# Power.net
KiCad netlist of a schematic drawn in Altium Designer
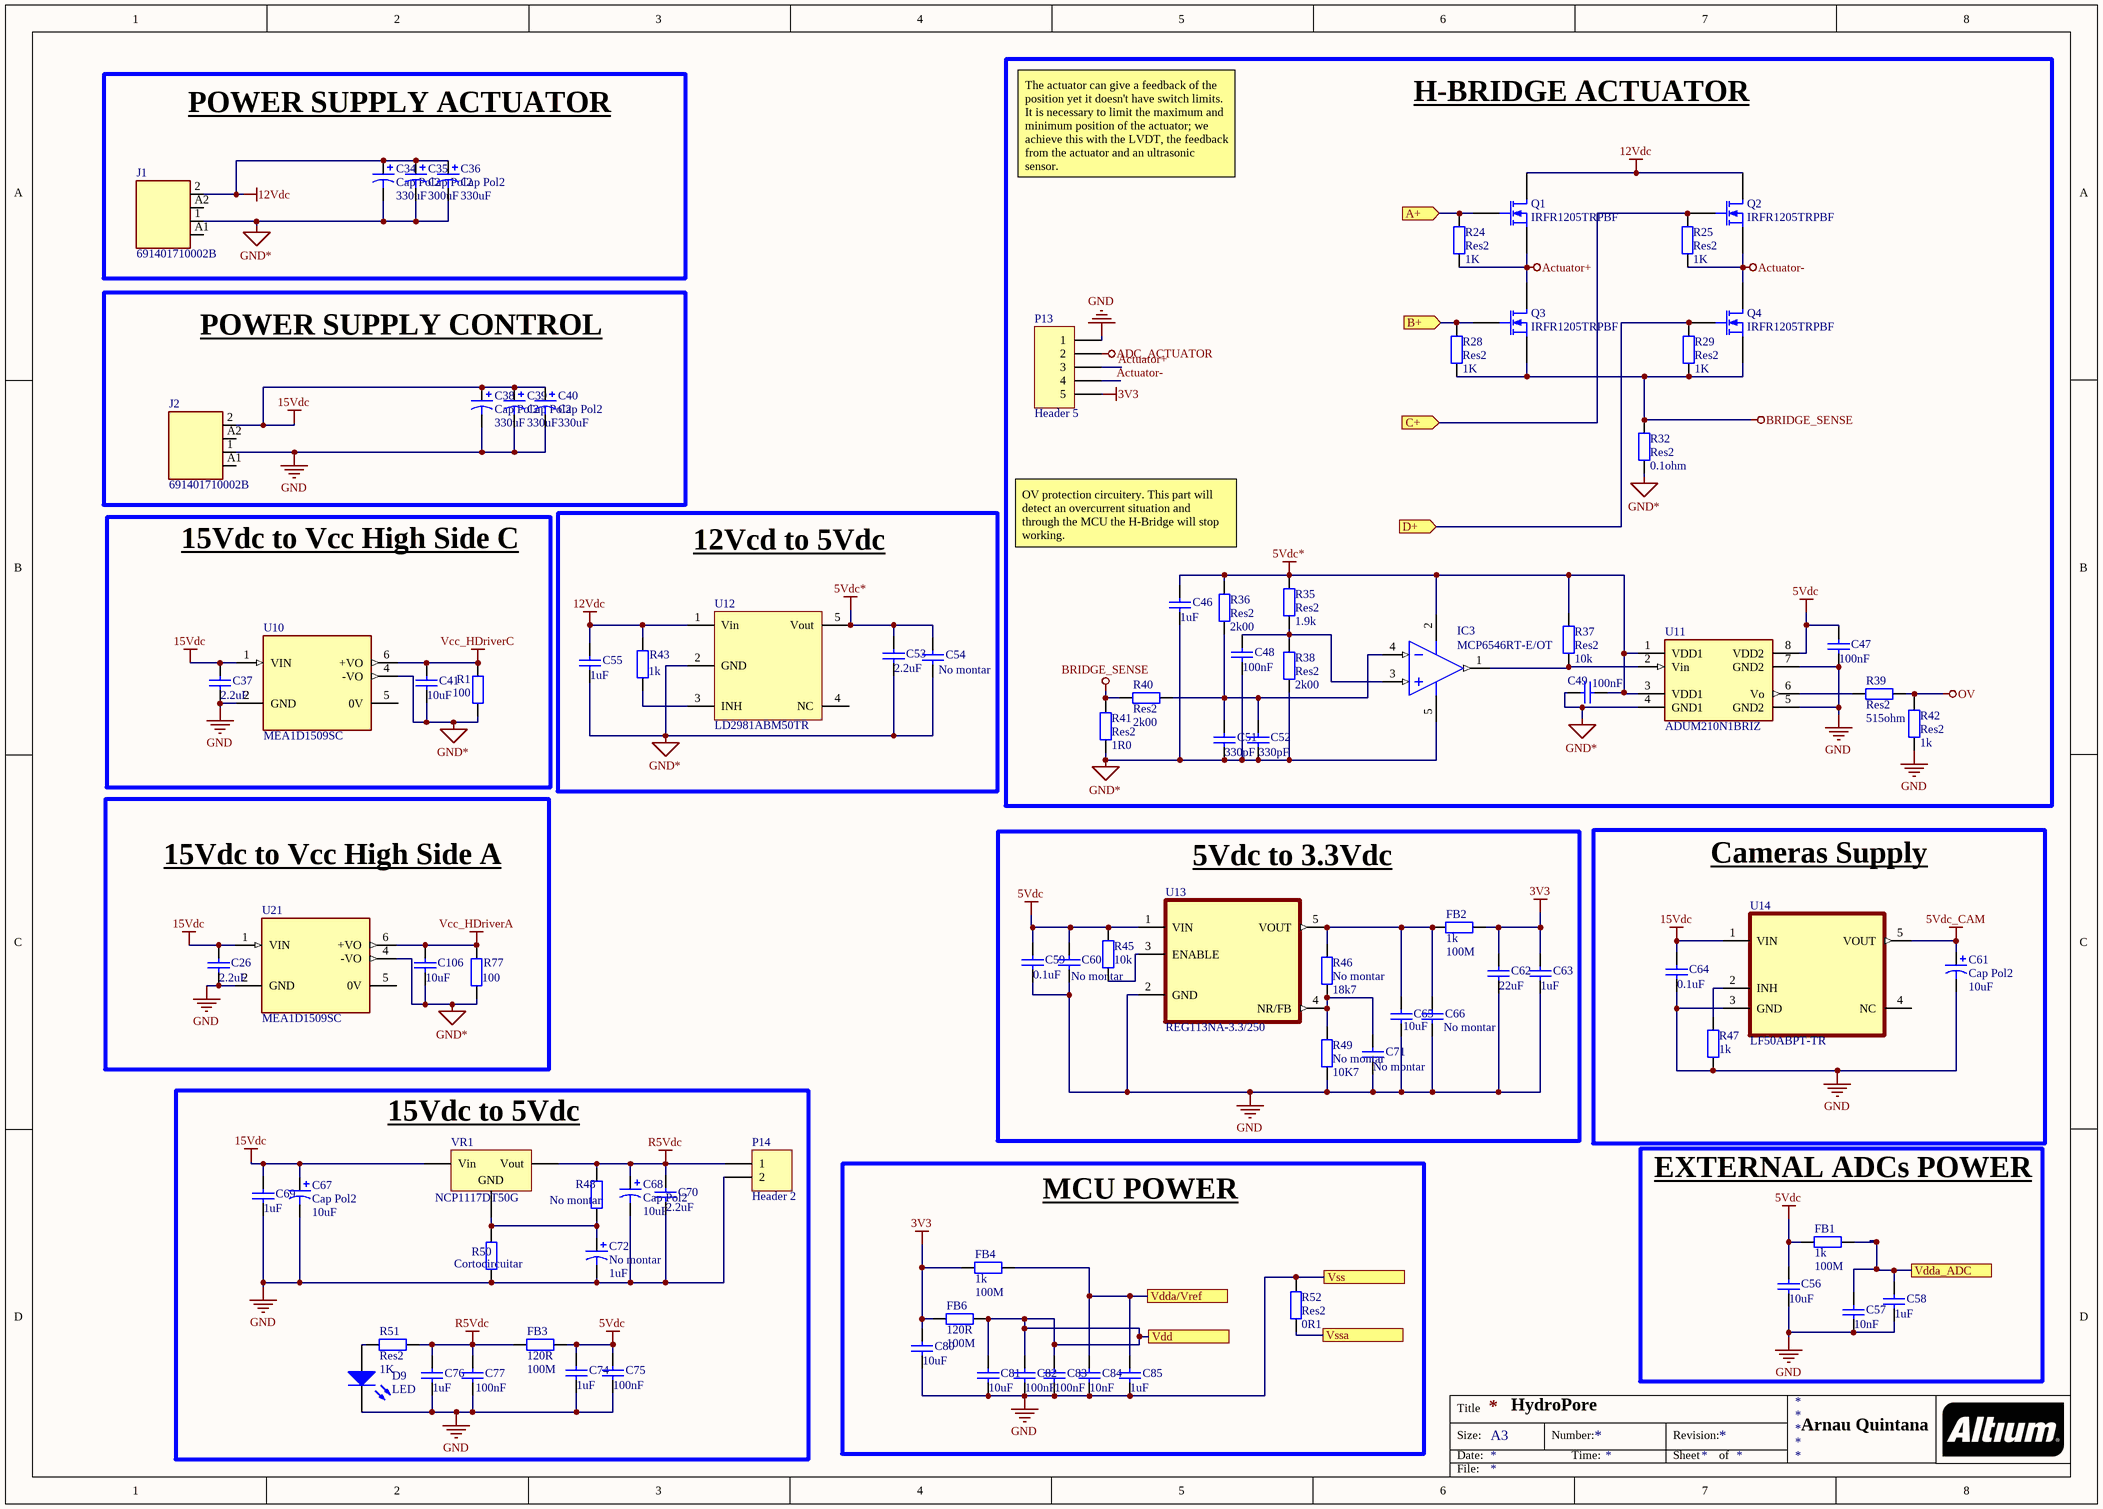
[diagram p0: Power.SchDoc]

(export (version "E")
  (design (tool "Eeschema 10.0.6"))
  (components
    (comp (ref "C26")
      (value "2.2uF")
      (footprint "Miscellaneous Devices:0603 - duplicate")
      (description "Capacitor")
      (fields (field (name "Comment") "Cap") (field (name "PUBLISHER") "Altium Limited"))
      (libsource (lib "Miscellaneous Devices") (part "Cap"))
    )
    (comp (ref "C34")
      (value "Cap Pol2")
      (footprint "Miscellaneous Devices:ElectrolythicCap_5mm")
      (description "Polarized Capacitor (Axial)")
      (fields (field (name "ALTIUM_VALUE") "330uF") (field (name "PUBLISHER") "Altium Limited"))
      (libsource (lib "Miscellaneous Devices") (part "Cap Pol2"))
    )
    (comp (ref "C35")
      (value "Cap Pol2")
      (footprint "Miscellaneous Devices:ElectrolythicCap_5mm")
      (description "Polarized Capacitor (Axial)")
      (fields (field (name "ALTIUM_VALUE") "300uF") (field (name "PUBLISHER") "Altium Limited"))
      (libsource (lib "Miscellaneous Devices") (part "Cap Pol2"))
    )
    (comp (ref "C36")
      (value "Cap Pol2")
      (footprint "Miscellaneous Devices:ElectrolythicCap_5mm")
      (description "Polarized Capacitor (Axial)")
      (fields (field (name "ALTIUM_VALUE") "330uF") (field (name "PUBLISHER") "Altium Limited"))
      (libsource (lib "Miscellaneous Devices") (part "Cap Pol2"))
    )
    (comp (ref "C37")
      (value "2.2uF")
      (footprint "Miscellaneous Devices:0603 - duplicate")
      (description "Capacitor")
      (fields (field (name "Comment") "Cap") (field (name "PUBLISHER") "Altium Limited"))
      (libsource (lib "Miscellaneous Devices") (part "Cap"))
    )
    (comp (ref "C38")
      (value "Cap Pol2")
      (footprint "Miscellaneous Devices:ElectrolythicCap_5mm")
      (description "Polarized Capacitor (Axial)")
      (fields (field (name "ALTIUM_VALUE") "330uF") (field (name "PUBLISHER") "Altium Limited"))
      (libsource (lib "Miscellaneous Devices") (part "Cap Pol2"))
    )
    (comp (ref "C39")
      (value "Cap Pol2")
      (footprint "Miscellaneous Devices:ElectrolythicCap_5mm")
      (description "Polarized Capacitor (Axial)")
      (fields (field (name "ALTIUM_VALUE") "330uF") (field (name "PUBLISHER") "Altium Limited"))
      (libsource (lib "Miscellaneous Devices") (part "Cap Pol2"))
    )
    (comp (ref "C40")
      (value "Cap Pol2")
      (footprint "Miscellaneous Devices:ElectrolythicCap_5mm")
      (description "Polarized Capacitor (Axial)")
      (fields (field (name "ALTIUM_VALUE") "330uF") (field (name "PUBLISHER") "Altium Limited"))
      (libsource (lib "Miscellaneous Devices") (part "Cap Pol2"))
    )
    (comp (ref "C41")
      (value "10uF")
      (footprint "Miscellaneous Devices:0603 - duplicate")
      (description "Capacitor")
      (fields (field (name "Comment") "Cap") (field (name "PUBLISHER") "Altium Limited"))
      (libsource (lib "Miscellaneous Devices") (part "Cap"))
    )
    (comp (ref "C46")
      (value "1uF")
      (footprint "Miscellaneous Devices:0603 - duplicate")
      (description "Capacitor")
      (fields (field (name "Comment") "Cap") (field (name "PUBLISHER") "Altium Limited"))
      (libsource (lib "Miscellaneous Devices") (part "Cap"))
    )
    (comp (ref "C47")
      (value "100nF")
      (footprint "Miscellaneous Devices:0603 - duplicate")
      (description "Capacitor")
      (fields (field (name "Comment") "Cap") (field (name "PUBLISHER") "Altium Limited"))
      (libsource (lib "Miscellaneous Devices") (part "Cap"))
    )
    (comp (ref "C48")
      (value "100nF")
      (footprint "Miscellaneous Devices:0603 - duplicate")
      (description "Capacitor")
      (fields (field (name "Comment") "Cap") (field (name "PUBLISHER") "Altium Limited"))
      (libsource (lib "Miscellaneous Devices") (part "Cap"))
    )
    (comp (ref "C49")
      (value "100nF")
      (footprint "Miscellaneous Devices:0603 - duplicate")
      (description "Capacitor")
      (fields (field (name "Comment") "Cap") (field (name "PUBLISHER") "Altium Limited"))
      (libsource (lib "Miscellaneous Devices") (part "Cap"))
    )
    (comp (ref "C51")
      (value "330pF")
      (footprint "Miscellaneous Devices:0603 - duplicate")
      (description "Capacitor")
      (fields (field (name "Comment") "Cap") (field (name "PUBLISHER") "Altium Limited"))
      (libsource (lib "Miscellaneous Devices") (part "Cap"))
    )
    (comp (ref "C52")
      (value "330pF")
      (footprint "Miscellaneous Devices:0603 - duplicate")
      (description "Capacitor")
      (fields (field (name "Comment") "Cap") (field (name "PUBLISHER") "Altium Limited"))
      (libsource (lib "Miscellaneous Devices") (part "Cap"))
    )
    (comp (ref "C53")
      (value "2.2uF")
      (footprint "Miscellaneous Devices:0603 - duplicate")
      (description "Capacitor")
      (fields (field (name "Comment") "Cap") (field (name "PUBLISHER") "Altium Limited"))
      (libsource (lib "Miscellaneous Devices") (part "Cap"))
    )
    (comp (ref "C54")
      (value "No montar")
      (footprint "Miscellaneous Devices:0603 - duplicate")
      (description "Capacitor")
      (fields (field (name "PUBLISHER") "Altium Limited"))
      (libsource (lib "Miscellaneous Devices") (part "Cap"))
    )
    (comp (ref "C55")
      (value "1uF")
      (footprint "Miscellaneous Devices:0603 - duplicate")
      (description "Capacitor")
      (fields (field (name "Comment") "Cap") (field (name "PUBLISHER") "Altium Limited"))
      (libsource (lib "Miscellaneous Devices") (part "Cap"))
    )
    (comp (ref "C56")
      (value "10uF")
      (footprint "Miscellaneous Devices:0603 - duplicate")
      (description "Capacitor")
      (fields (field (name "Comment") "Cap") (field (name "PUBLISHER") "Altium Limited"))
      (libsource (lib "Miscellaneous Devices") (part "Cap"))
    )
    (comp (ref "C57")
      (value "10nF")
      (footprint "Miscellaneous Devices:0603 - duplicate")
      (description "Capacitor")
      (fields (field (name "Comment") "Cap") (field (name "PUBLISHER") "Altium Limited"))
      (libsource (lib "Miscellaneous Devices") (part "Cap"))
    )
    (comp (ref "C58")
      (value "1uF")
      (footprint "Miscellaneous Devices:0603 - duplicate")
      (description "Capacitor")
      (fields (field (name "Comment") "Cap") (field (name "PUBLISHER") "Altium Limited"))
      (libsource (lib "Miscellaneous Devices") (part "Cap"))
    )
    (comp (ref "C59")
      (value "0.1uF")
      (footprint "Miscellaneous Devices:0603 - duplicate")
      (description "Capacitor")
      (fields (field (name "Comment") "Cap") (field (name "PUBLISHER") "Altium Limited"))
      (libsource (lib "Miscellaneous Devices") (part "Cap"))
    )
    (comp (ref "C60")
      (value "No montar")
      (footprint "Miscellaneous Devices:0603 - duplicate")
      (description "Capacitor")
      (fields (field (name "PUBLISHER") "Altium Limited"))
      (libsource (lib "Miscellaneous Devices") (part "Cap"))
    )
    (comp (ref "C61")
      (value "Cap Pol2")
      (footprint "Miscellaneous Devices:ElectrolythicCap_2mm")
      (description "Polarized Capacitor (Axial)")
      (fields (field (name "ALTIUM_VALUE") "10uF") (field (name "PUBLISHER") "Altium Limited"))
      (libsource (lib "Miscellaneous Devices") (part "Cap Pol2"))
    )
    (comp (ref "C62")
      (value "22uF")
      (footprint "Miscellaneous Devices:0603 - duplicate")
      (description "Capacitor")
      (fields (field (name "Comment") "Cap") (field (name "PUBLISHER") "Altium Limited"))
      (libsource (lib "Miscellaneous Devices") (part "Cap"))
    )
    (comp (ref "C63")
      (value "1uF")
      (footprint "Miscellaneous Devices:0603 - duplicate")
      (description "Capacitor")
      (fields (field (name "Comment") "Cap") (field (name "PUBLISHER") "Altium Limited"))
      (libsource (lib "Miscellaneous Devices") (part "Cap"))
    )
    (comp (ref "C64")
      (value "0.1uF")
      (footprint "Miscellaneous Devices:0603 - duplicate")
      (description "Capacitor")
      (fields (field (name "Comment") "Cap") (field (name "PUBLISHER") "Altium Limited"))
      (libsource (lib "Miscellaneous Devices") (part "Cap"))
    )
    (comp (ref "C65")
      (value "10uF")
      (footprint "Miscellaneous Devices:0603 - duplicate")
      (description "Capacitor")
      (fields (field (name "PUBLISHER") "Altium Limited"))
      (libsource (lib "Miscellaneous Devices") (part "Cap"))
    )
    (comp (ref "C66")
      (value "No montar")
      (footprint "Miscellaneous Devices:0603 - duplicate")
      (description "Capacitor")
      (fields (field (name "PUBLISHER") "Altium Limited"))
      (libsource (lib "Miscellaneous Devices") (part "Cap"))
    )
    (comp (ref "C67")
      (value "Cap Pol2")
      (footprint "Miscellaneous Devices:ElectrolythicCap_2mm")
      (description "Polarized Capacitor (Axial)")
      (fields (field (name "ALTIUM_VALUE") "10uF") (field (name "PUBLISHER") "Altium Limited"))
      (libsource (lib "Miscellaneous Devices") (part "Cap Pol2"))
    )
    (comp (ref "C68")
      (value "Cap Pol2")
      (footprint "Miscellaneous Devices:ElectrolythicCap_2mm")
      (description "Polarized Capacitor (Axial)")
      (fields (field (name "ALTIUM_VALUE") "10uF") (field (name "PUBLISHER") "Altium Limited"))
      (libsource (lib "Miscellaneous Devices") (part "Cap Pol2"))
    )
    (comp (ref "C69")
      (value "1uF")
      (footprint "Miscellaneous Devices:0603 - duplicate")
      (description "Capacitor")
      (fields (field (name "Comment") "Cap") (field (name "PUBLISHER") "Altium Limited"))
      (libsource (lib "Miscellaneous Devices") (part "Cap"))
    )
    (comp (ref "C70")
      (value "2.2uF")
      (footprint "Miscellaneous Devices:0603 - duplicate")
      (description "Capacitor")
      (fields (field (name "Comment") "Cap") (field (name "PUBLISHER") "Altium Limited"))
      (libsource (lib "Miscellaneous Devices") (part "Cap"))
    )
    (comp (ref "C71")
      (value "No montar")
      (footprint "Miscellaneous Devices:0603 - duplicate")
      (description "Capacitor")
      (fields (field (name "Comment") "0.01uF") (field (name "PUBLISHER") "Altium Limited"))
      (libsource (lib "Miscellaneous Devices") (part "Cap"))
    )
    (comp (ref "C72")
      (value "No montar")
      (footprint "Miscellaneous Devices:ElectrolythicCap_2mm")
      (description "Polarized Capacitor (Axial)")
      (fields (field (name "ALTIUM_VALUE") "1uF") (field (name "PUBLISHER") "Altium Limited"))
      (libsource (lib "Miscellaneous Devices") (part "Cap Pol2"))
    )
    (comp (ref "C74")
      (value "1uF")
      (footprint "Miscellaneous Devices:0603 - duplicate")
      (description "Capacitor")
      (fields (field (name "Comment") "Cap") (field (name "PUBLISHER") "Altium Limited"))
      (libsource (lib "Miscellaneous Devices") (part "Cap"))
    )
    (comp (ref "C75")
      (value "100nF")
      (footprint "Miscellaneous Devices:0603 - duplicate")
      (description "Capacitor")
      (fields (field (name "Comment") "Cap") (field (name "PUBLISHER") "Altium Limited"))
      (libsource (lib "Miscellaneous Devices") (part "Cap"))
    )
    (comp (ref "C76")
      (value "1uF")
      (footprint "Miscellaneous Devices:0603 - duplicate")
      (description "Capacitor")
      (fields (field (name "Comment") "Cap") (field (name "PUBLISHER") "Altium Limited"))
      (libsource (lib "Miscellaneous Devices") (part "Cap"))
    )
    (comp (ref "C77")
      (value "100nF")
      (footprint "Miscellaneous Devices:0603 - duplicate")
      (description "Capacitor")
      (fields (field (name "Comment") "Cap") (field (name "PUBLISHER") "Altium Limited"))
      (libsource (lib "Miscellaneous Devices") (part "Cap"))
    )
    (comp (ref "C80")
      (value "10uF")
      (footprint "Miscellaneous Devices:0603 - duplicate")
      (description "Capacitor")
      (fields (field (name "Comment") "Cap") (field (name "PUBLISHER") "Altium Limited"))
      (libsource (lib "Miscellaneous Devices") (part "Cap"))
    )
    (comp (ref "C81")
      (value "10uF")
      (footprint "Miscellaneous Devices:0603 - duplicate")
      (description "Capacitor")
      (fields (field (name "Comment") "Cap") (field (name "PUBLISHER") "Altium Limited"))
      (libsource (lib "Miscellaneous Devices") (part "Cap"))
    )
    (comp (ref "C82")
      (value "100nF")
      (footprint "Miscellaneous Devices:0603 - duplicate")
      (description "Capacitor")
      (fields (field (name "Comment") "Cap") (field (name "PUBLISHER") "Altium Limited"))
      (libsource (lib "Miscellaneous Devices") (part "Cap"))
    )
    (comp (ref "C83")
      (value "100nF")
      (footprint "Miscellaneous Devices:0603 - duplicate")
      (description "Capacitor")
      (fields (field (name "Comment") "Cap") (field (name "PUBLISHER") "Altium Limited"))
      (libsource (lib "Miscellaneous Devices") (part "Cap"))
    )
    (comp (ref "C84")
      (value "10nF")
      (footprint "Miscellaneous Devices:0603 - duplicate")
      (description "Capacitor")
      (fields (field (name "Comment") "Cap") (field (name "PUBLISHER") "Altium Limited"))
      (libsource (lib "Miscellaneous Devices") (part "Cap"))
    )
    (comp (ref "C85")
      (value "1uF")
      (footprint "Miscellaneous Devices:0603 - duplicate")
      (description "Capacitor")
      (fields (field (name "Comment") "Cap") (field (name "PUBLISHER") "Altium Limited"))
      (libsource (lib "Miscellaneous Devices") (part "Cap"))
    )
    (comp (ref "C106")
      (value "10uF")
      (footprint "Miscellaneous Devices:0603 - duplicate")
      (description "Capacitor")
      (fields (field (name "Comment") "Cap") (field (name "PUBLISHER") "Altium Limited"))
      (libsource (lib "Miscellaneous Devices") (part "Cap"))
    )
    (comp (ref "D9")
      (value "LED")
      (footprint "Miscellaneous Devices:LED 1206")
      (description "Typical RED, GREEN, YELLOW, AMBER GaAs LED")
      (fields (field (name "PUBLISHER") "Altium Limited"))
      (libsource (lib "Miscellaneous Devices") (part "LED"))
    )
    (comp (ref "FB1")
      (value "1k")
      (footprint "Miscellaneous Devices:0603 - duplicate")
      (description "Resistor")
      (fields (field (name "ALTIUM_VALUE") "100M") (field (name "PUBLISHER") "Altium Limited"))
      (libsource (lib "") (part "Res2_2"))
    )
    (comp (ref "FB2")
      (value "1k")
      (footprint "Miscellaneous Devices:0603 - duplicate")
      (description "Resistor")
      (fields (field (name "ALTIUM_VALUE") "100M") (field (name "PUBLISHER") "Altium Limited"))
      (libsource (lib "") (part "Res2_2"))
    )
    (comp (ref "FB3")
      (value "120R")
      (footprint "Miscellaneous Devices:0603 - duplicate")
      (description "Resistor")
      (fields (field (name "ALTIUM_VALUE") "100M") (field (name "PUBLISHER") "Altium Limited"))
      (libsource (lib "") (part "Res2_2"))
    )
    (comp (ref "FB4")
      (value "1k")
      (footprint "Miscellaneous Devices:0603 - duplicate")
      (description "Resistor")
      (fields (field (name "ALTIUM_VALUE") "100M") (field (name "PUBLISHER") "Altium Limited"))
      (libsource (lib "") (part "Res2_2"))
    )
    (comp (ref "FB6")
      (value "120R")
      (footprint "Miscellaneous Devices:0603 - duplicate")
      (description "Resistor")
      (fields (field (name "ALTIUM_VALUE") "100M") (field (name "PUBLISHER") "Altium Limited"))
      (libsource (lib "") (part "Res2_2"))
    )
    (comp (ref "IC3")
      (value "MCP6546RT-E/OT")
      (footprint "Miscellaneous Devices:SOT23-5_N")
      (description "Operational Amplifier")
      (fields (field (name "PUBLISHER") "Altium Limited"))
      (libsource (lib "Miscellaneous Devices") (part "MCP6546RT-E/OT"))
    )
    (comp (ref "J1")
      (value "691401710002B")
      (footprint "Miscellaneous Connectors:691401710002B")
      (fields (field (name "MF") "WÃ¼rth Elektronik"))
      (libsource (lib "Miscellaneous Connectors") (part "691401710002B"))
    )
    (comp (ref "J2")
      (value "691401710002B")
      (footprint "Miscellaneous Connectors:691401710002B")
      (fields (field (name "MF") "WÃ¼rth Elektronik"))
      (libsource (lib "Miscellaneous Connectors") (part "691401710002B"))
    )
    (comp (ref "P13")
      (value "Header 5")
      (footprint "Miscellaneous Connectors:regleta_5")
      (description "Header, 5-Pin")
      (fields (field (name "PUBLISHER") "Altium Limited"))
      (libsource (lib "Miscellaneous Connectors") (part "Header 5"))
    )
    (comp (ref "P14")
      (value "Header 2")
      (footprint "HDR1X2")
      (description "Header, 2-Pin")
      (fields (field (name "PUBLISHER") "Altium Limited"))
      (libsource (lib "Miscellaneous Connectors") (part "Header 2"))
    )
    (comp (ref "Q1")
      (value "IRFR1205TRPBF")
      (footprint "Miscellaneous Devices:Infineon_PG-TO252-3_MFG")
      (description "N-Channel MOSFET")
      (fields (field (name "PUBLISHER") "Altium Limited"))
      (libsource (lib "Miscellaneous Devices") (part "IRFR1205TRPBF"))
    )
    (comp (ref "Q2")
      (value "IRFR1205TRPBF")
      (footprint "Miscellaneous Devices:Infineon_PG-TO252-3_MFG")
      (description "N-Channel MOSFET")
      (fields (field (name "PUBLISHER") "Altium Limited"))
      (libsource (lib "Miscellaneous Devices") (part "IRFR1205TRPBF"))
    )
    (comp (ref "Q3")
      (value "IRFR1205TRPBF")
      (footprint "Miscellaneous Devices:Infineon_PG-TO252-3_MFG")
      (description "N-Channel MOSFET")
      (fields (field (name "PUBLISHER") "Altium Limited"))
      (libsource (lib "Miscellaneous Devices") (part "IRFR1205TRPBF"))
    )
    (comp (ref "Q4")
      (value "IRFR1205TRPBF")
      (footprint "Miscellaneous Devices:Infineon_PG-TO252-3_MFG")
      (description "N-Channel MOSFET")
      (fields (field (name "PUBLISHER") "Altium Limited"))
      (libsource (lib "Miscellaneous Devices") (part "IRFR1205TRPBF"))
    )
    (comp (ref "R1")
      (value "100")
      (footprint "Miscellaneous Devices:1206")
      (description "Resistor")
      (fields (field (name "PUBLISHER") "Altium Limited"))
      (libsource (lib "Miscellaneous Devices") (part "Res2"))
    )
    (comp (ref "R24")
      (value "Res2")
      (footprint "Miscellaneous Devices:0603 - duplicate")
      (description "Resistor")
      (fields (field (name "ALTIUM_VALUE") "1K") (field (name "PUBLISHER") "Altium Limited"))
      (libsource (lib "Miscellaneous Devices") (part "Res2"))
    )
    (comp (ref "R25")
      (value "Res2")
      (footprint "Miscellaneous Devices:0603 - duplicate")
      (description "Resistor")
      (fields (field (name "ALTIUM_VALUE") "1K") (field (name "PUBLISHER") "Altium Limited"))
      (libsource (lib "Miscellaneous Devices") (part "Res2"))
    )
    (comp (ref "R28")
      (value "Res2")
      (footprint "Miscellaneous Devices:0603 - duplicate")
      (description "Resistor")
      (fields (field (name "ALTIUM_VALUE") "1K") (field (name "PUBLISHER") "Altium Limited"))
      (libsource (lib "Miscellaneous Devices") (part "Res2"))
    )
    (comp (ref "R29")
      (value "Res2")
      (footprint "Miscellaneous Devices:0603 - duplicate")
      (description "Resistor")
      (fields (field (name "ALTIUM_VALUE") "1K") (field (name "PUBLISHER") "Altium Limited"))
      (libsource (lib "Miscellaneous Devices") (part "Res2"))
    )
    (comp (ref "R32")
      (value "Res2")
      (footprint "Miscellaneous Devices:1206")
      (description "Resistor")
      (fields (field (name "ALTIUM_VALUE") "0.1ohm") (field (name "PUBLISHER") "Altium Limited"))
      (libsource (lib "Miscellaneous Devices") (part "Res2"))
    )
    (comp (ref "R35")
      (value "Res2")
      (footprint "Miscellaneous Devices:0603 - duplicate")
      (description "Resistor")
      (fields (field (name "ALTIUM_VALUE") "1.9k") (field (name "PUBLISHER") "Altium Limited"))
      (libsource (lib "") (part "Res2_3"))
    )
    (comp (ref "R36")
      (value "Res2")
      (footprint "Miscellaneous Devices:0603 - duplicate")
      (description "Resistor")
      (fields (field (name "ALTIUM_VALUE") "2k00") (field (name "PUBLISHER") "Altium Limited"))
      (libsource (lib "") (part "Res2_3"))
    )
    (comp (ref "R37")
      (value "Res2")
      (footprint "Miscellaneous Devices:0603 - duplicate")
      (description "Resistor")
      (fields (field (name "ALTIUM_VALUE") "10k") (field (name "PUBLISHER") "Altium Limited"))
      (libsource (lib "Miscellaneous Devices") (part "Res2"))
    )
    (comp (ref "R38")
      (value "Res2")
      (footprint "Miscellaneous Devices:0603 - duplicate")
      (description "Resistor")
      (fields (field (name "ALTIUM_VALUE") "2k00") (field (name "PUBLISHER") "Altium Limited"))
      (libsource (lib "") (part "Res2_3"))
    )
    (comp (ref "R39")
      (value "Res2")
      (footprint "Miscellaneous Devices:0603 - duplicate")
      (description "Resistor")
      (fields (field (name "ALTIUM_VALUE") "515ohm") (field (name "PUBLISHER") "Altium Limited"))
      (libsource (lib "") (part "Res2_1"))
    )
    (comp (ref "R40")
      (value "Res2")
      (footprint "Miscellaneous Devices:0603 - duplicate")
      (description "Resistor")
      (fields (field (name "ALTIUM_VALUE") "2k00") (field (name "PUBLISHER") "Altium Limited"))
      (libsource (lib "") (part "Res2_2"))
    )
    (comp (ref "R41")
      (value "Res2")
      (footprint "Miscellaneous Devices:1206")
      (description "Resistor")
      (fields (field (name "ALTIUM_VALUE") "1R0") (field (name "PUBLISHER") "Altium Limited"))
      (libsource (lib "Miscellaneous Devices") (part "Res2"))
    )
    (comp (ref "R42")
      (value "Res2")
      (footprint "Miscellaneous Devices:0603 - duplicate")
      (description "Resistor")
      (fields (field (name "ALTIUM_VALUE") "1k") (field (name "PUBLISHER") "Altium Limited"))
      (libsource (lib "") (part "Res2_3"))
    )
    (comp (ref "R43")
      (value "1k")
      (footprint "Miscellaneous Devices:0603 - duplicate")
      (description "Resistor")
      (fields (field (name "PUBLISHER") "Altium Limited"))
      (libsource (lib "Miscellaneous Devices") (part "Res2"))
    )
    (comp (ref "R45")
      (value "10k")
      (footprint "Miscellaneous Devices:0603 - duplicate")
      (description "Resistor")
      (fields (field (name "PUBLISHER") "Altium Limited"))
      (libsource (lib "Miscellaneous Devices") (part "Res2"))
    )
    (comp (ref "R46")
      (value "No montar")
      (footprint "Miscellaneous Devices:0603 - duplicate")
      (description "Resistor")
      (fields (field (name "ALTIUM_VALUE") "18k7") (field (name "PUBLISHER") "Altium Limited"))
      (libsource (lib "Miscellaneous Devices") (part "Res2"))
    )
    (comp (ref "R47")
      (value "1k")
      (footprint "Miscellaneous Devices:0603 - duplicate")
      (description "Resistor")
      (fields (field (name "PUBLISHER") "Altium Limited"))
      (libsource (lib "Miscellaneous Devices") (part "Res2"))
    )
    (comp (ref "R48")
      (value "No montar")
      (footprint "Miscellaneous Devices:0603 - duplicate")
      (description "Resistor")
      (fields (field (name "PUBLISHER") "Altium Limited"))
      (libsource (lib "Miscellaneous Devices") (part "Res2"))
    )
    (comp (ref "R49")
      (value "No montar")
      (footprint "Miscellaneous Devices:0603 - duplicate")
      (description "Resistor")
      (fields (field (name "ALTIUM_VALUE") "10K7") (field (name "PUBLISHER") "Altium Limited"))
      (libsource (lib "Miscellaneous Devices") (part "Res2"))
    )
    (comp (ref "R50")
      (value "Cortocircuitar")
      (footprint "Miscellaneous Devices:0603 - duplicate")
      (description "Resistor")
      (fields (field (name "PUBLISHER") "Altium Limited"))
      (libsource (lib "Miscellaneous Devices") (part "Res2"))
    )
    (comp (ref "R51")
      (value "Res2")
      (footprint "Miscellaneous Devices:0603 - duplicate")
      (description "Resistor")
      (fields (field (name "ALTIUM_VALUE") "1K") (field (name "PUBLISHER") "Altium Limited"))
      (libsource (lib "") (part "Res2_2"))
    )
    (comp (ref "R52")
      (value "Res2")
      (footprint "Miscellaneous Devices:0603 - duplicate")
      (description "Resistor")
      (fields (field (name "ALTIUM_VALUE") "0R1") (field (name "PUBLISHER") "Altium Limited"))
      (libsource (lib "Miscellaneous Devices") (part "Res2"))
    )
    (comp (ref "R77")
      (value "100")
      (footprint "Miscellaneous Devices:1206")
      (description "Resistor")
      (fields (field (name "PUBLISHER") "Altium Limited"))
      (libsource (lib "Miscellaneous Devices") (part "Res2"))
    )
    (comp (ref "U10")
      (value "MEA1D1509SC")
      (footprint "Miscellaneous Devices:CONV_MEA1D1509SC")
      (description "1 W, Dual Independent Output, 7 Pin SIP, 4200 Vdc Isolation, Dc-Dc Converter")
      (fields (field (name "MP") "VQA-S15-D15-SIP") (field (name "MF") "CUI Inc."))
      (libsource (lib "Miscellaneous Devices") (part "MEA1D1509SC"))
    )
    (comp (ref "U11")
      (value "ADUM210N1BRIZ")
      (footprint "Miscellaneous Devices:SOIC127P1031X265-8N")
      (description "Digital Isolator")
      (fields (field (name "MP") "PEME2-S15-D5-S") (field (name "MF") "CUI"))
      (libsource (lib "Miscellaneous Devices") (part "ADUM210N1BRIZ"))
    )
    (comp (ref "U12")
      (value "LD2981ABM50TR")
      (footprint "Miscellaneous Devices:SOT23-5_N")
      (fields (field (name "PUBLISHER") "Altium Limited"))
      (libsource (lib "Miscellaneous Devices") (part "LD2981ABM50TR"))
    )
    (comp (ref "U13")
      (value "REG113NA-3.3/250")
      (footprint "Miscellaneous Devices:SOT23-5_N")
      (description "Dropout Linear  Regulator")
      (fields (field (name "MP") "LP3964EMP-ADJ"))
      (libsource (lib "Miscellaneous Devices") (part "REG113NA-3.3/250"))
    )
    (comp (ref "U14")
      (value "LF50ABPT-TR")
      (footprint "Miscellaneous Devices:DPAK114P990X239-6N")
      (description "Dropout Linear  Regulator")
      (fields (field (name "MP") "LP3964EMP-ADJ"))
      (libsource (lib "Miscellaneous Devices") (part "LF50ABPT-TR"))
    )
    (comp (ref "U21")
      (value "MEA1D1509SC")
      (footprint "Miscellaneous Devices:CONV_MEA1D1509SC")
      (description "1 W, Dual Independent Output, 7 Pin SIP, 4200 Vdc Isolation, Dc-Dc Converter")
      (fields (field (name "MP") "VQA-S15-D15-SIP") (field (name "MF") "CUI Inc."))
      (libsource (lib "Miscellaneous Devices") (part "MEA1D1509SC"))
    )
    (comp (ref "VR1")
      (value "NCP1117DT50G")
      (footprint "D2PAK_N")
      (fields (field (name "PUBLISHER") "Altium Limited"))
      (libsource (lib "Miscellaneous Devices") (part "Volt Reg"))
    )
  )
  (nets
    (net (code "1") (name "/A+") (class "Default")
      (node (ref "Q1") (pin "1") (pinfunction "G_1") (pintype "passive"))
      (node (ref "R24") (pin "2") (pinfunction "2_2") (pintype "passive"))
    )
    (net (code "2") (name "/B+") (class "Default")
      (node (ref "Q3") (pin "1") (pinfunction "G_1") (pintype "passive"))
      (node (ref "R28") (pin "2") (pinfunction "2_2") (pintype "passive"))
    )
    (net (code "3") (name "/C+") (class "Default")
      (node (ref "Q2") (pin "1") (pinfunction "G_1") (pintype "passive"))
      (node (ref "R25") (pin "2") (pinfunction "2_2") (pintype "passive"))
    )
    (net (code "4") (name "/D+") (class "Default")
      (node (ref "Q4") (pin "1") (pinfunction "G_1") (pintype "passive"))
      (node (ref "R29") (pin "2") (pinfunction "2_2") (pintype "passive"))
    )
    (net (code "5") (name "/Vdd") (class "Default")
      (node (ref "C81") (pin "2") (pinfunction "2_2") (pintype "passive"))
      (node (ref "C82") (pin "2") (pinfunction "2_2") (pintype "passive"))
      (node (ref "C83") (pin "2") (pinfunction "2_2") (pintype "passive"))
      (node (ref "FB6") (pin "2") (pinfunction "2_2") (pintype "passive"))
    )
    (net (code "6") (name "/Vdda_ADC") (class "Default")
      (node (ref "C57") (pin "2") (pinfunction "2_2") (pintype "passive"))
      (node (ref "C58") (pin "2") (pinfunction "2_2") (pintype "passive"))
      (node (ref "FB1") (pin "2") (pinfunction "2_2") (pintype "passive"))
    )
    (net (code "7") (name "/Vdda{slash}Vref") (class "Default")
      (node (ref "C84") (pin "2") (pinfunction "2_2") (pintype "passive"))
      (node (ref "C85") (pin "2") (pinfunction "2_2") (pintype "passive"))
      (node (ref "FB4") (pin "2") (pinfunction "2_2") (pintype "passive"))
    )
    (net (code "8") (name "/Vssa") (class "Default")
      (node (ref "R52") (pin "1") (pinfunction "1_1") (pintype "passive"))
    )
    (net (code "9") (name "3V3") (class "Default")
      (node (ref "C62") (pin "2") (pinfunction "2_2") (pintype "passive"))
      (node (ref "C63") (pin "2") (pinfunction "2_2") (pintype "passive"))
      (node (ref "C80") (pin "2") (pinfunction "2_2") (pintype "passive"))
      (node (ref "FB2") (pin "2") (pinfunction "2_2") (pintype "passive"))
      (node (ref "FB4") (pin "1") (pinfunction "1_1") (pintype "passive"))
      (node (ref "FB6") (pin "1") (pinfunction "1_1") (pintype "passive"))
      (node (ref "P13") (pin "5") (pinfunction "5_5") (pintype "passive"))
    )
    (net (code "10") (name "5Vdc") (class "Default")
      (node (ref "C47") (pin "2") (pinfunction "2_2") (pintype "passive"))
      (node (ref "C56") (pin "2") (pinfunction "2_2") (pintype "passive"))
      (node (ref "C59") (pin "2") (pinfunction "2_2") (pintype "passive"))
      (node (ref "C60") (pin "2") (pinfunction "2_2") (pintype "passive"))
      (node (ref "C74") (pin "2") (pinfunction "2_2") (pintype "passive"))
      (node (ref "C75") (pin "2") (pinfunction "2_2") (pintype "passive"))
      (node (ref "FB1") (pin "1") (pinfunction "1_1") (pintype "passive"))
      (node (ref "FB3") (pin "2") (pinfunction "2_2") (pintype "passive"))
      (node (ref "R45") (pin "2") (pinfunction "2_2") (pintype "passive"))
      (node (ref "U11") (pin "8") (pinfunction "VDD2_8") (pintype "power_in"))
      (node (ref "U13") (pin "1") (pinfunction "VIN_1") (pintype "power_in"))
    )
    (net (code "11") (name "5Vdc*") (class "Default")
      (node (ref "C46") (pin "2") (pinfunction "2_2") (pintype "passive"))
      (node (ref "C49") (pin "1") (pinfunction "1_1") (pintype "passive"))
      (node (ref "C53") (pin "2") (pinfunction "2_2") (pintype "passive"))
      (node (ref "C54") (pin "2") (pinfunction "2_2") (pintype "passive"))
      (node (ref "IC3") (pin "2") (pinfunction "V+_2") (pintype "power_in"))
      (node (ref "R35") (pin "1") (pinfunction "1_1") (pintype "passive"))
      (node (ref "R36") (pin "1") (pinfunction "1_1") (pintype "passive"))
      (node (ref "R37") (pin "2") (pinfunction "2_2") (pintype "passive"))
      (node (ref "U11") (pin "1") (pinfunction "VDD1_1") (pintype "power_in"))
      (node (ref "U11") (pin "3") (pinfunction "VDD1_3") (pintype "power_in"))
      (node (ref "U12") (pin "5") (pinfunction "Vout_5") (pintype "passive"))
    )
    (net (code "12") (name "5Vdc_CAM") (class "Default")
      (node (ref "C61") (pin "P") (pinfunction "1_P") (pintype "passive"))
      (node (ref "U14") (pin "5") (pinfunction "VOUT_5") (pintype "output"))
    )
    (net (code "13") (name "12Vdc") (class "Default")
      (node (ref "C34") (pin "P") (pinfunction "1_P") (pintype "passive"))
      (node (ref "C35") (pin "P") (pinfunction "1_P") (pintype "passive"))
      (node (ref "C36") (pin "P") (pinfunction "1_P") (pintype "passive"))
      (node (ref "C55") (pin "2") (pinfunction "2_2") (pintype "passive"))
      (node (ref "J1") (pin "2") (pinfunction "1_2") (pintype "passive"))
      (node (ref "Q1") (pin "2") (pinfunction "D_2") (pintype "passive"))
      (node (ref "Q2") (pin "2") (pinfunction "D_2") (pintype "passive"))
      (node (ref "R43") (pin "2") (pinfunction "2_2") (pintype "passive"))
      (node (ref "U12") (pin "1") (pinfunction "Vin_1") (pintype "passive"))
    )
    (net (code "14") (name "15Vdc") (class "Default")
      (node (ref "C26") (pin "2") (pinfunction "2_2") (pintype "passive"))
      (node (ref "C37") (pin "2") (pinfunction "2_2") (pintype "passive"))
      (node (ref "C38") (pin "P") (pinfunction "1_P") (pintype "passive"))
      (node (ref "C39") (pin "P") (pinfunction "1_P") (pintype "passive"))
      (node (ref "C40") (pin "P") (pinfunction "1_P") (pintype "passive"))
      (node (ref "C64") (pin "2") (pinfunction "2_2") (pintype "passive"))
      (node (ref "C67") (pin "P") (pinfunction "1_P") (pintype "passive"))
      (node (ref "C69") (pin "2") (pinfunction "2_2") (pintype "passive"))
      (node (ref "J2") (pin "2") (pinfunction "1_2") (pintype "passive"))
      (node (ref "U10") (pin "1") (pinfunction "VIN_1") (pintype "input"))
      (node (ref "U14") (pin "1") (pinfunction "VIN_1") (pintype "power_in"))
      (node (ref "U21") (pin "1") (pinfunction "VIN_1") (pintype "input"))
      (node (ref "VR1") (pin "3") (pinfunction "Vin_3") (pintype "passive"))
    )
    (net (code "15") (name "ADC_ACTUATOR") (class "Default")
      (node (ref "P13") (pin "2") (pinfunction "2_2") (pintype "passive"))
    )
    (net (code "16") (name "Actuator+") (class "Default")
      (node (ref "P13") (pin "3") (pinfunction "3_3") (pintype "passive"))
      (node (ref "Q1") (pin "3") (pinfunction "S_3") (pintype "passive"))
      (node (ref "Q3") (pin "2") (pinfunction "D_2") (pintype "passive"))
      (node (ref "R24") (pin "1") (pinfunction "1_1") (pintype "passive"))
    )
    (net (code "17") (name "Actuator-") (class "Default")
      (node (ref "P13") (pin "4") (pinfunction "4_4") (pintype "passive"))
      (node (ref "Q2") (pin "3") (pinfunction "S_3") (pintype "passive"))
      (node (ref "Q4") (pin "2") (pinfunction "D_2") (pintype "passive"))
      (node (ref "R25") (pin "1") (pinfunction "1_1") (pintype "passive"))
    )
    (net (code "18") (name "BRIDGE_SENSE") (class "Default")
      (node (ref "Q3") (pin "3") (pinfunction "S_3") (pintype "passive"))
      (node (ref "Q4") (pin "3") (pinfunction "S_3") (pintype "passive"))
      (node (ref "R28") (pin "1") (pinfunction "1_1") (pintype "passive"))
      (node (ref "R29") (pin "1") (pinfunction "1_1") (pintype "passive"))
      (node (ref "R32") (pin "2") (pinfunction "2_2") (pintype "passive"))
      (node (ref "R40") (pin "1") (pinfunction "1_1") (pintype "passive"))
      (node (ref "R41") (pin "2") (pinfunction "2_2") (pintype "passive"))
    )
    (net (code "19") (name "GND") (class "Default")
      (node (ref "C26") (pin "1") (pinfunction "1_1") (pintype "passive"))
      (node (ref "C37") (pin "1") (pinfunction "1_1") (pintype "passive"))
      (node (ref "C38") (pin "N") (pinfunction "2_N") (pintype "passive"))
      (node (ref "C39") (pin "N") (pinfunction "2_N") (pintype "passive"))
      (node (ref "C40") (pin "N") (pinfunction "2_N") (pintype "passive"))
      (node (ref "C47") (pin "1") (pinfunction "1_1") (pintype "passive"))
      (node (ref "C56") (pin "1") (pinfunction "1_1") (pintype "passive"))
      (node (ref "C57") (pin "1") (pinfunction "1_1") (pintype "passive"))
      (node (ref "C58") (pin "1") (pinfunction "1_1") (pintype "passive"))
      (node (ref "C59") (pin "1") (pinfunction "1_1") (pintype "passive"))
      (node (ref "C60") (pin "1") (pinfunction "1_1") (pintype "passive"))
      (node (ref "C61") (pin "N") (pinfunction "2_N") (pintype "passive"))
      (node (ref "C62") (pin "1") (pinfunction "1_1") (pintype "passive"))
      (node (ref "C63") (pin "1") (pinfunction "1_1") (pintype "passive"))
      (node (ref "C64") (pin "1") (pinfunction "1_1") (pintype "passive"))
      (node (ref "C65") (pin "1") (pinfunction "1_1") (pintype "passive"))
      (node (ref "C66") (pin "1") (pinfunction "1_1") (pintype "passive"))
      (node (ref "C67") (pin "N") (pinfunction "2_N") (pintype "passive"))
      (node (ref "C68") (pin "N") (pinfunction "2_N") (pintype "passive"))
      (node (ref "C69") (pin "1") (pinfunction "1_1") (pintype "passive"))
      (node (ref "C70") (pin "1") (pinfunction "1_1") (pintype "passive"))
      (node (ref "C71") (pin "1") (pinfunction "1_1") (pintype "passive"))
      (node (ref "C72") (pin "N") (pinfunction "2_N") (pintype "passive"))
      (node (ref "C74") (pin "1") (pinfunction "1_1") (pintype "passive"))
      (node (ref "C75") (pin "1") (pinfunction "1_1") (pintype "passive"))
      (node (ref "C76") (pin "1") (pinfunction "1_1") (pintype "passive"))
      (node (ref "C77") (pin "1") (pinfunction "1_1") (pintype "passive"))
      (node (ref "C80") (pin "1") (pinfunction "1_1") (pintype "passive"))
      (node (ref "C81") (pin "1") (pinfunction "1_1") (pintype "passive"))
      (node (ref "C82") (pin "1") (pinfunction "1_1") (pintype "passive"))
      (node (ref "C83") (pin "1") (pinfunction "1_1") (pintype "passive"))
      (node (ref "C84") (pin "1") (pinfunction "1_1") (pintype "passive"))
      (node (ref "C85") (pin "1") (pinfunction "1_1") (pintype "passive"))
      (node (ref "D9") (pin "2") (pinfunction "K_2") (pintype "passive"))
      (node (ref "J2") (pin "1") (pinfunction "2_1") (pintype "passive"))
      (node (ref "P13") (pin "1") (pinfunction "1_1") (pintype "passive"))
      (node (ref "P14") (pin "2") (pinfunction "2_2") (pintype "passive"))
      (node (ref "R42") (pin "2") (pinfunction "2_2") (pintype "passive"))
      (node (ref "R47") (pin "1") (pinfunction "1_1") (pintype "passive"))
      (node (ref "R49") (pin "1") (pinfunction "1_1") (pintype "passive"))
      (node (ref "R50") (pin "1") (pinfunction "1_1") (pintype "passive"))
      (node (ref "R52") (pin "2") (pinfunction "2_2") (pintype "passive"))
      (node (ref "U10") (pin "2") (pinfunction "GND_2") (pintype "power_in"))
      (node (ref "U11") (pin "5") (pinfunction "GND2_5") (pintype "power_in"))
      (node (ref "U11") (pin "7") (pinfunction "GND2_7") (pintype "power_in"))
      (node (ref "U13") (pin "2") (pinfunction "GND_2") (pintype "passive"))
      (node (ref "U14") (pin "3") (pinfunction "GND_3") (pintype "passive"))
      (node (ref "U21") (pin "2") (pinfunction "GND_2") (pintype "power_in"))
    )
    (net (code "20") (name "GND*") (class "Default")
      (node (ref "C106") (pin "1") (pinfunction "1_1") (pintype "passive"))
      (node (ref "C34") (pin "N") (pinfunction "2_N") (pintype "passive"))
      (node (ref "C35") (pin "N") (pinfunction "2_N") (pintype "passive"))
      (node (ref "C36") (pin "N") (pinfunction "2_N") (pintype "passive"))
      (node (ref "C41") (pin "1") (pinfunction "1_1") (pintype "passive"))
      (node (ref "C46") (pin "1") (pinfunction "1_1") (pintype "passive"))
      (node (ref "C48") (pin "1") (pinfunction "1_1") (pintype "passive"))
      (node (ref "C49") (pin "2") (pinfunction "2_2") (pintype "passive"))
      (node (ref "C51") (pin "1") (pinfunction "1_1") (pintype "passive"))
      (node (ref "C52") (pin "1") (pinfunction "1_1") (pintype "passive"))
      (node (ref "C53") (pin "1") (pinfunction "1_1") (pintype "passive"))
      (node (ref "C54") (pin "1") (pinfunction "1_1") (pintype "passive"))
      (node (ref "C55") (pin "1") (pinfunction "1_1") (pintype "passive"))
      (node (ref "IC3") (pin "5") (pinfunction "V-_5") (pintype "power_in"))
      (node (ref "J1") (pin "1") (pinfunction "2_1") (pintype "passive"))
      (node (ref "R1") (pin "1") (pinfunction "1_1") (pintype "passive"))
      (node (ref "R32") (pin "1") (pinfunction "1_1") (pintype "passive"))
      (node (ref "R38") (pin "2") (pinfunction "2_2") (pintype "passive"))
      (node (ref "R41") (pin "1") (pinfunction "1_1") (pintype "passive"))
      (node (ref "R77") (pin "1") (pinfunction "1_1") (pintype "passive"))
      (node (ref "U10") (pin "4") (pinfunction "-VO_4") (pintype "output"))
      (node (ref "U11") (pin "4") (pinfunction "GND1_4") (pintype "power_in"))
      (node (ref "U12") (pin "2") (pinfunction "GND_2") (pintype "passive"))
      (node (ref "U21") (pin "4") (pinfunction "-VO_4") (pintype "output"))
    )
    (net (code "21") (name "Net-(C72-1)") (class "Default")
      (node (ref "C72") (pin "P") (pinfunction "1_P") (pintype "passive"))
      (node (ref "R48") (pin "1") (pinfunction "1_1") (pintype "passive"))
      (node (ref "R50") (pin "2") (pinfunction "2_2") (pintype "passive"))
      (node (ref "VR1") (pin "1") (pinfunction "GND_1") (pintype "passive"))
    )
    (net (code "22") (name "Net-(D9-A)") (class "Default")
      (node (ref "D9") (pin "1") (pinfunction "A_1") (pintype "passive"))
      (node (ref "R51") (pin "1") (pinfunction "1_1") (pintype "passive"))
    )
    (net (code "23") (name "Net-(IC3-IN+)") (class "Default")
      (node (ref "C48") (pin "2") (pinfunction "2_2") (pintype "passive"))
      (node (ref "IC3") (pin "3") (pinfunction "IN+_3") (pintype "input"))
      (node (ref "R35") (pin "2") (pinfunction "2_2") (pintype "passive"))
      (node (ref "R38") (pin "1") (pinfunction "1_1") (pintype "passive"))
    )
    (net (code "24") (name "Net-(IC3-IN-)") (class "Default")
      (node (ref "C51") (pin "2") (pinfunction "2_2") (pintype "passive"))
      (node (ref "C52") (pin "2") (pinfunction "2_2") (pintype "passive"))
      (node (ref "IC3") (pin "4") (pinfunction "IN-_4") (pintype "input"))
      (node (ref "R36") (pin "2") (pinfunction "2_2") (pintype "passive"))
      (node (ref "R40") (pin "2") (pinfunction "2_2") (pintype "passive"))
    )
    (net (code "25") (name "Net-(IC3-OUT)") (class "Default")
      (node (ref "IC3") (pin "1") (pinfunction "OUT_1") (pintype "output"))
      (node (ref "R37") (pin "1") (pinfunction "1_1") (pintype "passive"))
      (node (ref "U11") (pin "2") (pinfunction "Vin_2") (pintype "input"))
    )
    (net (code "26") (name "Net-(U11-Vo)") (class "Default")
      (node (ref "R39") (pin "2") (pinfunction "2_2") (pintype "passive"))
      (node (ref "U11") (pin "6") (pinfunction "Vo_6") (pintype "output"))
    )
    (net (code "27") (name "Net-(U12-INH)") (class "Default")
      (node (ref "R43") (pin "1") (pinfunction "1_1") (pintype "passive"))
      (node (ref "U12") (pin "3") (pinfunction "INH_3") (pintype "passive"))
    )
    (net (code "28") (name "Net-(U13-ENABLE)") (class "Default")
      (node (ref "R45") (pin "1") (pinfunction "1_1") (pintype "passive"))
      (node (ref "U13") (pin "3") (pinfunction "ENABLE_3") (pintype "passive"))
    )
    (net (code "29") (name "Net-(U13-NR{slash}FB)") (class "Default")
      (node (ref "C71") (pin "2") (pinfunction "2_2") (pintype "passive"))
      (node (ref "R46") (pin "1") (pinfunction "1_1") (pintype "passive"))
      (node (ref "R49") (pin "2") (pinfunction "2_2") (pintype "passive"))
      (node (ref "U13") (pin "4") (pinfunction "NR/FB_4") (pintype "output"))
    )
    (net (code "30") (name "Net-(U13-VOUT)") (class "Default")
      (node (ref "C65") (pin "2") (pinfunction "2_2") (pintype "passive"))
      (node (ref "C66") (pin "2") (pinfunction "2_2") (pintype "passive"))
      (node (ref "FB2") (pin "1") (pinfunction "1_1") (pintype "passive"))
      (node (ref "R46") (pin "2") (pinfunction "2_2") (pintype "passive"))
      (node (ref "U13") (pin "5") (pinfunction "VOUT_5") (pintype "output"))
    )
    (net (code "31") (name "Net-(U14-INH)") (class "Default")
      (node (ref "R47") (pin "2") (pinfunction "2_2") (pintype "passive"))
      (node (ref "U14") (pin "2") (pinfunction "INH_2") (pintype "passive"))
    )
    (net (code "32") (name "OV") (class "Default")
      (node (ref "R39") (pin "1") (pinfunction "1_1") (pintype "passive"))
      (node (ref "R42") (pin "1") (pinfunction "1_1") (pintype "passive"))
    )
    (net (code "33") (name "R5Vdc") (class "Default")
      (node (ref "C68") (pin "P") (pinfunction "1_P") (pintype "passive"))
      (node (ref "C70") (pin "2") (pinfunction "2_2") (pintype "passive"))
      (node (ref "C76") (pin "2") (pinfunction "2_2") (pintype "passive"))
      (node (ref "C77") (pin "2") (pinfunction "2_2") (pintype "passive"))
      (node (ref "FB3") (pin "1") (pinfunction "1_1") (pintype "passive"))
      (node (ref "P14") (pin "1") (pinfunction "1_1") (pintype "passive"))
      (node (ref "R48") (pin "2") (pinfunction "2_2") (pintype "passive"))
      (node (ref "R51") (pin "2") (pinfunction "2_2") (pintype "passive"))
      (node (ref "VR1") (pin "2") (pinfunction "Vout_2") (pintype "passive"))
    )
    (net (code "34") (name "Vcc_HDriverA") (class "Default")
      (node (ref "C106") (pin "2") (pinfunction "2_2") (pintype "passive"))
      (node (ref "R77") (pin "2") (pinfunction "2_2") (pintype "passive"))
      (node (ref "U21") (pin "6") (pinfunction "+VO_6") (pintype "output"))
    )
    (net (code "35") (name "Vcc_HDriverC") (class "Default")
      (node (ref "C41") (pin "2") (pinfunction "2_2") (pintype "passive"))
      (node (ref "R1") (pin "2") (pinfunction "2_2") (pintype "passive"))
      (node (ref "U10") (pin "6") (pinfunction "+VO_6") (pintype "output"))
    )
    (net (code "36") (name "unconnected-(J1-1-PadA2)") (class "Default")
      (node (ref "J1") (pin "A2") (pinfunction "1_A2") (pintype "passive"))
    )
    (net (code "37") (name "unconnected-(J1-2-PadA1)") (class "Default")
      (node (ref "J1") (pin "A1") (pinfunction "2_A1") (pintype "passive"))
    )
    (net (code "38") (name "unconnected-(J2-1-PadA2)") (class "Default")
      (node (ref "J2") (pin "A2") (pinfunction "1_A2") (pintype "passive"))
    )
    (net (code "39") (name "unconnected-(J2-2-PadA1)") (class "Default")
      (node (ref "J2") (pin "A1") (pinfunction "2_A1") (pintype "passive"))
    )
    (net (code "40") (name "unconnected-(U10-0V-Pad5)") (class "Default")
      (node (ref "U10") (pin "5") (pinfunction "0V_5") (pintype "power_in"))
    )
    (net (code "41") (name "unconnected-(U12-NC-Pad4)") (class "Default")
      (node (ref "U12") (pin "4") (pinfunction "NC_4") (pintype "passive"))
    )
    (net (code "42") (name "unconnected-(U14-NC-Pad4)") (class "Default")
      (node (ref "U14") (pin "4") (pinfunction "NC_4") (pintype "passive"))
    )
    (net (code "43") (name "unconnected-(U21-0V-Pad5)") (class "Default")
      (node (ref "U21") (pin "5") (pinfunction "0V_5") (pintype "power_in"))
    )
  )
)
